# V3_USB.net
KiCad netlist of a schematic drawn in Altium Designer
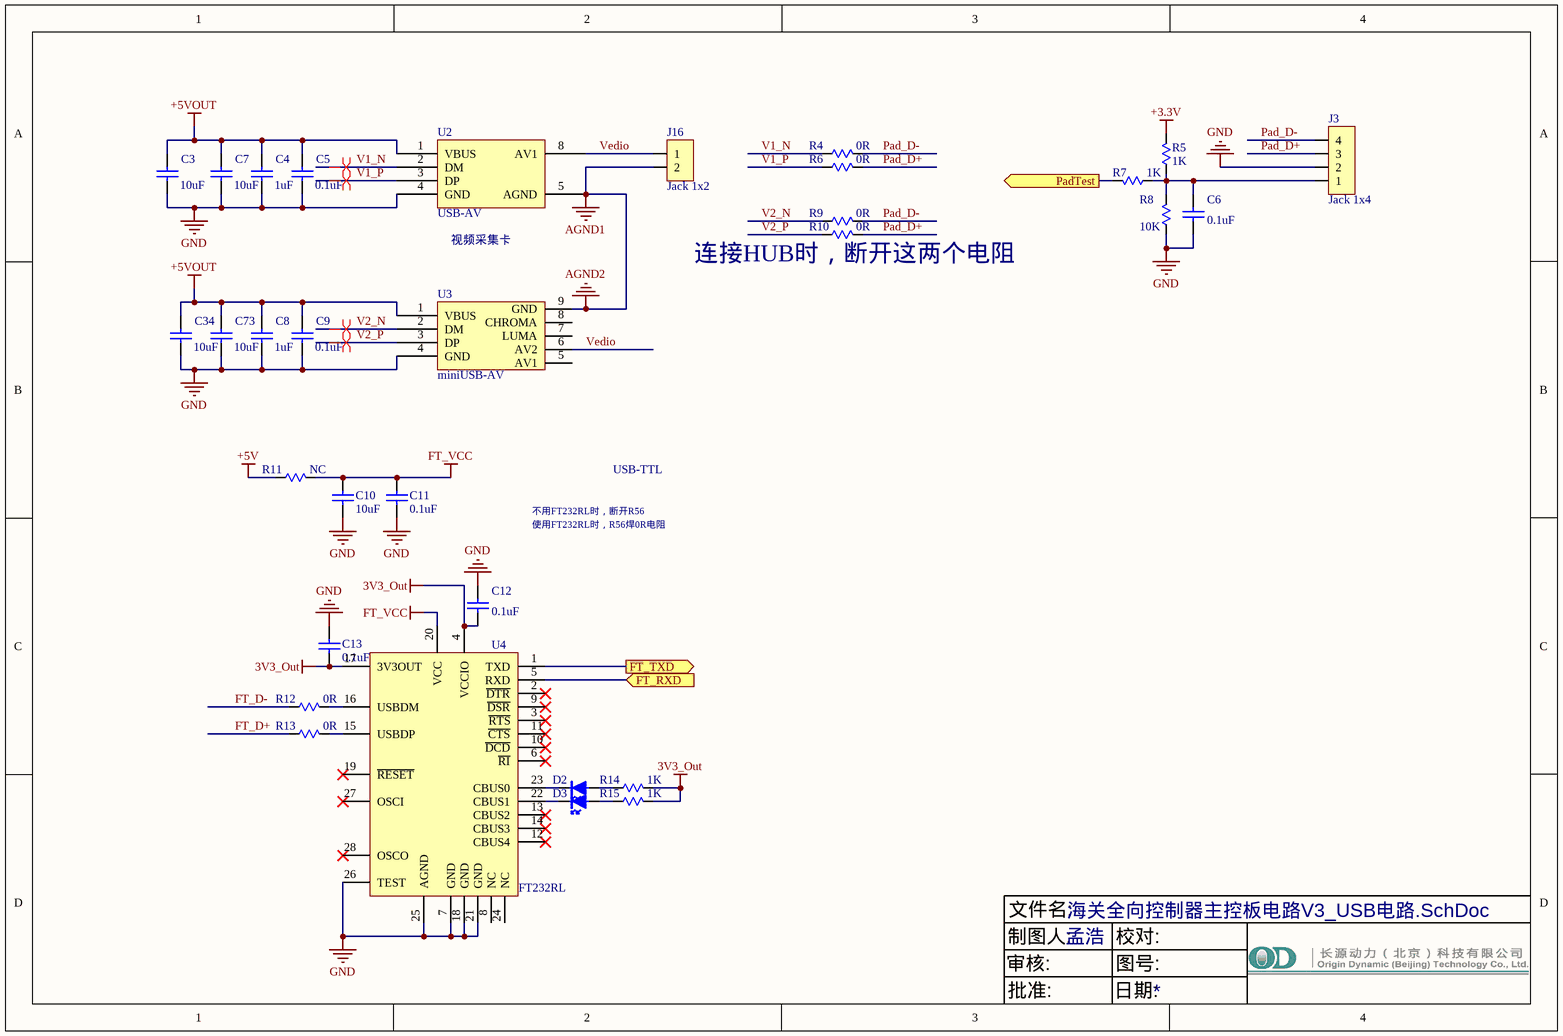
[diagram p0: 海关全向控制器主控板电路V3_USB电路.SchDoc]

(export (version "E")
  (design (tool "Eeschema 10.0.6"))
  (components
    (comp (ref "C3")
      (value "10uF")
      (footprint "C0805")
      (description "CAP")
      (fields (field (name "PUBLISHER") "Altium Limited"))
      (libsource (lib "Passive Components Class") (part "CAP"))
    )
    (comp (ref "C4")
      (value "1uF")
      (footprint "C0805")
      (description "CAP")
      (fields (field (name "PUBLISHER") "Altium Limited"))
      (libsource (lib "Passive Components Class") (part "CAP"))
    )
    (comp (ref "C5") (value "0.1uF") (footprint "C0805") (libsource (lib "SMD") (part "Cap Semi")))
    (comp (ref "C6")
      (value "0.1uF")
      (footprint "C0805")
      (description "Capacitor")
      (fields (field (name "PUBLISHER") "Altium Limited"))
      (libsource (lib "Miscellaneous Devices") (part "Cap"))
    )
    (comp (ref "C7")
      (value "10uF")
      (footprint "C0805")
      (description "CAP")
      (fields (field (name "PUBLISHER") "Altium Limited"))
      (libsource (lib "Passive Components Class") (part "CAP"))
    )
    (comp (ref "C8")
      (value "1uF")
      (footprint "C0805")
      (description "CAP")
      (fields (field (name "PUBLISHER") "Altium Limited"))
      (libsource (lib "Passive Components Class") (part "CAP"))
    )
    (comp (ref "C9") (value "0.1uF") (footprint "C0805") (libsource (lib "SMD") (part "Cap Semi")))
    (comp (ref "C10")
      (value "10uF")
      (footprint "C0805")
      (description "CAP")
      (fields (field (name "PUBLISHER") "Altium Limited"))
      (libsource (lib "Passive Components Class") (part "CAP"))
    )
    (comp (ref "C11") (value "0.1uF") (footprint "C0805") (libsource (lib "SMD") (part "Cap Semi")))
    (comp (ref "C12")
      (value "0.1uF")
      (footprint "C0805")
      (description "Capacitor")
      (fields (field (name "PUBLISHER") "Altium Limited"))
      (libsource (lib "Miscellaneous Devices") (part "Cap"))
    )
    (comp (ref "C13") (value "0.1uF") (footprint "C0805") (libsource (lib "SMD") (part "Cap Semi")))
    (comp (ref "C34")
      (value "10uF")
      (footprint "C0805")
      (description "CAP")
      (fields (field (name "PUBLISHER") "Altium Limited"))
      (libsource (lib "Passive Components Class") (part "CAP"))
    )
    (comp (ref "C73")
      (value "10uF")
      (footprint "C0805")
      (description "CAP")
      (fields (field (name "PUBLISHER") "Altium Limited"))
      (libsource (lib "Passive Components Class") (part "CAP"))
    )
    (comp (ref "D2")
      (value "LED")
      (footprint "LED0603")
      (libsource (lib "Passive Components Class") (part "LED"))
    )
    (comp (ref "D3")
      (value "LED")
      (footprint "LED0603")
      (libsource (lib "Passive Components Class") (part "LED"))
    )
    (comp (ref "J3")
      (value "Jack 1x4")
      (footprint "35363-0460")
      (description "插座")
      (libsource (lib "Connector") (part "Jack 1x4"))
    )
    (comp (ref "J16")
      (value "Jack 1x2")
      (footprint "35363-0260")
      (description "插座")
      (libsource (lib "Connector") (part "Jack 1x2"))
    )
    (comp (ref "R4")
      (value "0R")
      (footprint "R0805")
      (description "Resistor")
      (fields (field (name "PUBLISHER") "Altium Limited"))
      (libsource (lib "Temp") (part "Res"))
    )
    (comp (ref "R5")
      (value "1K")
      (footprint "R0805")
      (description "Resistor")
      (fields (field (name "PUBLISHER") "Altium Limited"))
      (libsource (lib "Temp") (part "Res"))
    )
    (comp (ref "R6")
      (value "0R")
      (footprint "R0805")
      (description "Resistor")
      (fields (field (name "PUBLISHER") "Altium Limited"))
      (libsource (lib "Temp") (part "Res"))
    )
    (comp (ref "R7")
      (value "1K")
      (footprint "R0805")
      (description "Resistor")
      (fields (field (name "PUBLISHER") "Altium Limited"))
      (libsource (lib "Temp") (part "Res"))
    )
    (comp (ref "R8")
      (value "10K")
      (footprint "R0805")
      (description "Resistor")
      (fields (field (name "PUBLISHER") "Altium Limited"))
      (libsource (lib "Temp") (part "Res"))
    )
    (comp (ref "R9")
      (value "0R")
      (footprint "R0805")
      (description "Resistor")
      (fields (field (name "PUBLISHER") "Altium Limited"))
      (libsource (lib "Temp") (part "Res"))
    )
    (comp (ref "R10")
      (value "0R")
      (footprint "R0805")
      (description "Resistor")
      (fields (field (name "PUBLISHER") "Altium Limited"))
      (libsource (lib "Temp") (part "Res"))
    )
    (comp (ref "R11")
      (value "NC")
      (footprint "R0805")
      (description "Resistor")
      (fields (field (name "PUBLISHER") "Altium Limited"))
      (libsource (lib "Temp") (part "Res"))
    )
    (comp (ref "R12")
      (value "0R")
      (footprint "R0805")
      (description "Resistor")
      (fields (field (name "PUBLISHER") "Altium Limited"))
      (libsource (lib "Temp") (part "Res"))
    )
    (comp (ref "R13")
      (value "0R")
      (footprint "R0805")
      (description "Resistor")
      (fields (field (name "PUBLISHER") "Altium Limited"))
      (libsource (lib "Temp") (part "Res"))
    )
    (comp (ref "R14")
      (value "1K")
      (footprint "R0805")
      (description "Resistor")
      (fields (field (name "PUBLISHER") "Altium Limited"))
      (libsource (lib "Temp") (part "Res"))
    )
    (comp (ref "R15")
      (value "1K")
      (footprint "R0805")
      (description "Resistor")
      (fields (field (name "PUBLISHER") "Altium Limited"))
      (libsource (lib "Temp") (part "Res"))
    )
    (comp (ref "U2") (value "USB-AV") (footprint "USB-AV") (libsource (lib "Module") (part "USB-AV")))
    (comp (ref "U3")
      (value "miniUSB-AV")
      (footprint "miniUSB-AV")
      (libsource (lib "Module") (part "miniUSB-AV"))
    )
    (comp (ref "U4")
      (value "FT232RL")
      (footprint "SSOP-28")
      (libsource (lib "海关全向控制器主控板V2") (part "FT232RL"))
    )
  )
  (nets
    (net (code "1") (name "+3.3V") (class "Default")
      (node (ref "R5") (pin "1") (pinfunction "1_1") (pintype "passive"))
    )
    (net (code "2") (name "+5V") (class "Default")
      (node (ref "R11") (pin "2") (pinfunction "2_2") (pintype "passive"))
    )
    (net (code "3") (name "+5VOUT") (class "Default")
      (node (ref "C3") (pin "1") (pinfunction "1_1") (pintype "passive"))
      (node (ref "C34") (pin "1") (pinfunction "1_1") (pintype "passive"))
      (node (ref "C4") (pin "1") (pinfunction "1_1") (pintype "passive"))
      (node (ref "C5") (pin "2") (pinfunction "2_2") (pintype "passive"))
      (node (ref "C7") (pin "1") (pinfunction "1_1") (pintype "passive"))
      (node (ref "C73") (pin "1") (pinfunction "1_1") (pintype "passive"))
      (node (ref "C8") (pin "1") (pinfunction "1_1") (pintype "passive"))
      (node (ref "C9") (pin "2") (pinfunction "2_2") (pintype "passive"))
      (node (ref "U2") (pin "1") (pinfunction "VBUS_1") (pintype "passive"))
      (node (ref "U3") (pin "1") (pinfunction "VBUS_1") (pintype "passive"))
    )
    (net (code "4") (name "/FT_D+") (class "Default")
      (node (ref "R13") (pin "2") (pinfunction "2_2") (pintype "passive"))
    )
    (net (code "5") (name "/FT_D-") (class "Default")
      (node (ref "R12") (pin "2") (pinfunction "2_2") (pintype "passive"))
    )
    (net (code "6") (name "/FT_RXD") (class "Default")
      (node (ref "U4") (pin "5") (pinfunction "RXD_5") (pintype "passive"))
    )
    (net (code "7") (name "/FT_TXD") (class "Default")
      (node (ref "U4") (pin "1") (pinfunction "TXD_1") (pintype "passive"))
    )
    (net (code "8") (name "/PadTest") (class "Default")
      (node (ref "R7") (pin "1") (pinfunction "1_1") (pintype "passive"))
    )
    (net (code "9") (name "/Pad_D+") (class "Default")
      (node (ref "J3") (pin "3") (pinfunction "3_3") (pintype "passive"))
      (node (ref "R10") (pin "1") (pinfunction "1_1") (pintype "passive"))
      (node (ref "R6") (pin "1") (pinfunction "1_1") (pintype "passive"))
    )
    (net (code "10") (name "/Pad_D-") (class "Default")
      (node (ref "J3") (pin "4") (pinfunction "4_4") (pintype "passive"))
      (node (ref "R4") (pin "1") (pinfunction "1_1") (pintype "passive"))
      (node (ref "R9") (pin "1") (pinfunction "1_1") (pintype "passive"))
    )
    (net (code "11") (name "/V1_N") (class "Default")
      (node (ref "R4") (pin "2") (pinfunction "2_2") (pintype "passive"))
      (node (ref "U2") (pin "2") (pinfunction "DM_2") (pintype "passive"))
    )
    (net (code "12") (name "/V1_P") (class "Default")
      (node (ref "R6") (pin "2") (pinfunction "2_2") (pintype "passive"))
      (node (ref "U2") (pin "3") (pinfunction "DP_3") (pintype "passive"))
    )
    (net (code "13") (name "/V2_N") (class "Default")
      (node (ref "R9") (pin "2") (pinfunction "2_2") (pintype "passive"))
      (node (ref "U3") (pin "2") (pinfunction "DM_2") (pintype "passive"))
    )
    (net (code "14") (name "/V2_P") (class "Default")
      (node (ref "R10") (pin "2") (pinfunction "2_2") (pintype "passive"))
      (node (ref "U3") (pin "3") (pinfunction "DP_3") (pintype "passive"))
    )
    (net (code "15") (name "/Vedio") (class "Default")
      (node (ref "J16") (pin "1") (pinfunction "1_1") (pintype "passive"))
      (node (ref "U2") (pin "8") (pinfunction "AV1_8") (pintype "passive"))
      (node (ref "U3") (pin "6") (pinfunction "AV2_6") (pintype "passive"))
    )
    (net (code "16") (name "3V3_Out") (class "Default")
      (node (ref "C12") (pin "2") (pinfunction "2_2") (pintype "passive"))
      (node (ref "C13") (pin "1") (pinfunction "1_1") (pintype "passive"))
      (node (ref "R14") (pin "1") (pinfunction "1_1") (pintype "passive"))
      (node (ref "R15") (pin "1") (pinfunction "1_1") (pintype "passive"))
      (node (ref "U4") (pin "17") (pinfunction "3V3OUT_17") (pintype "passive"))
      (node (ref "U4") (pin "4") (pinfunction "VCCIO_4") (pintype "passive"))
    )
    (net (code "17") (name "AGND1") (class "Default")
      (node (ref "J16") (pin "2") (pinfunction "2_2") (pintype "passive"))
      (node (ref "U2") (pin "5") (pinfunction "AGND_5") (pintype "passive"))
      (node (ref "U3") (pin "9") (pinfunction "GND_9") (pintype "passive"))
    )
    (net (code "18") (name "FT_VCC") (class "Default")
      (node (ref "C10") (pin "1") (pinfunction "1_1") (pintype "passive"))
      (node (ref "C11") (pin "2") (pinfunction "2_2") (pintype "passive"))
      (node (ref "R11") (pin "1") (pinfunction "1_1") (pintype "passive"))
      (node (ref "U4") (pin "20") (pinfunction "VCC_20") (pintype "passive"))
    )
    (net (code "19") (name "GND") (class "Default")
      (node (ref "C10") (pin "2") (pinfunction "2_2") (pintype "passive"))
      (node (ref "C11") (pin "1") (pinfunction "1_1") (pintype "passive"))
      (node (ref "C12") (pin "1") (pinfunction "1_1") (pintype "passive"))
      (node (ref "C13") (pin "2") (pinfunction "2_2") (pintype "passive"))
      (node (ref "C3") (pin "2") (pinfunction "2_2") (pintype "passive"))
      (node (ref "C34") (pin "2") (pinfunction "2_2") (pintype "passive"))
      (node (ref "C4") (pin "2") (pinfunction "2_2") (pintype "passive"))
      (node (ref "C5") (pin "1") (pinfunction "1_1") (pintype "passive"))
      (node (ref "C6") (pin "2") (pinfunction "2_2") (pintype "passive"))
      (node (ref "C7") (pin "2") (pinfunction "2_2") (pintype "passive"))
      (node (ref "C73") (pin "2") (pinfunction "2_2") (pintype "passive"))
      (node (ref "C8") (pin "2") (pinfunction "2_2") (pintype "passive"))
      (node (ref "C9") (pin "1") (pinfunction "1_1") (pintype "passive"))
      (node (ref "J3") (pin "2") (pinfunction "2_2") (pintype "passive"))
      (node (ref "R8") (pin "2") (pinfunction "2_2") (pintype "passive"))
      (node (ref "U2") (pin "4") (pinfunction "GND_4") (pintype "passive"))
      (node (ref "U3") (pin "4") (pinfunction "GND_4") (pintype "passive"))
      (node (ref "U4") (pin "18") (pinfunction "GND_18") (pintype "passive"))
      (node (ref "U4") (pin "21") (pinfunction "GND_21") (pintype "passive"))
      (node (ref "U4") (pin "25") (pinfunction "AGND_25") (pintype "passive"))
      (node (ref "U4") (pin "26") (pinfunction "TEST_26") (pintype "passive"))
      (node (ref "U4") (pin "7") (pinfunction "GND_7") (pintype "passive"))
    )
    (net (code "20") (name "Net-(C6-Pad1)") (class "Default")
      (node (ref "C6") (pin "1") (pinfunction "1_1") (pintype "passive"))
      (node (ref "J3") (pin "1") (pinfunction "1_1") (pintype "passive"))
      (node (ref "R5") (pin "2") (pinfunction "2_2") (pintype "passive"))
      (node (ref "R7") (pin "2") (pinfunction "2_2") (pintype "passive"))
      (node (ref "R8") (pin "1") (pinfunction "1_1") (pintype "passive"))
    )
    (net (code "21") (name "Net-(D2-A)") (class "Default")
      (node (ref "D2") (pin "1") (pinfunction "A_1") (pintype "passive"))
      (node (ref "R14") (pin "2") (pinfunction "2_2") (pintype "passive"))
    )
    (net (code "22") (name "Net-(D2-K)") (class "Default")
      (node (ref "D2") (pin "2") (pinfunction "K_2") (pintype "passive"))
      (node (ref "U4") (pin "23") (pinfunction "CBUS0_23") (pintype "passive"))
    )
    (net (code "23") (name "Net-(D3-A)") (class "Default")
      (node (ref "D3") (pin "1") (pinfunction "A_1") (pintype "passive"))
      (node (ref "R15") (pin "2") (pinfunction "2_2") (pintype "passive"))
    )
    (net (code "24") (name "Net-(D3-K)") (class "Default")
      (node (ref "D3") (pin "2") (pinfunction "K_2") (pintype "passive"))
      (node (ref "U4") (pin "22") (pinfunction "CBUS1_22") (pintype "passive"))
    )
    (net (code "25") (name "Net-(U4-USBDM)") (class "Default")
      (node (ref "R12") (pin "1") (pinfunction "1_1") (pintype "passive"))
      (node (ref "U4") (pin "16") (pinfunction "USBDM_16") (pintype "passive"))
    )
    (net (code "26") (name "Net-(U4-USBDP)") (class "Default")
      (node (ref "R13") (pin "1") (pinfunction "1_1") (pintype "passive"))
      (node (ref "U4") (pin "15") (pinfunction "USBDP_15") (pintype "passive"))
    )
    (net (code "27") (name "unconnected-(U3-AV1-Pad5)") (class "Default")
      (node (ref "U3") (pin "5") (pinfunction "AV1_5") (pintype "passive"))
    )
    (net (code "28") (name "unconnected-(U3-CHROMA-Pad8)") (class "Default")
      (node (ref "U3") (pin "8") (pinfunction "CHROMA_8") (pintype "passive"))
    )
    (net (code "29") (name "unconnected-(U3-LUMA-Pad7)") (class "Default")
      (node (ref "U3") (pin "7") (pinfunction "LUMA_7") (pintype "passive"))
    )
    (net (code "30") (name "unconnected-(U4-CBUS2-Pad13)") (class "Default")
      (node (ref "U4") (pin "13") (pinfunction "CBUS2_13") (pintype "passive+no_connect"))
    )
    (net (code "31") (name "unconnected-(U4-CBUS3-Pad14)") (class "Default")
      (node (ref "U4") (pin "14") (pinfunction "CBUS3_14") (pintype "passive+no_connect"))
    )
    (net (code "32") (name "unconnected-(U4-CBUS4-Pad12)") (class "Default")
      (node (ref "U4") (pin "12") (pinfunction "CBUS4_12") (pintype "passive+no_connect"))
    )
    (net (code "33") (name "unconnected-(U4-NC-Pad8)") (class "Default")
      (node (ref "U4") (pin "8") (pinfunction "NC_8") (pintype "passive"))
    )
    (net (code "34") (name "unconnected-(U4-NC-Pad24)") (class "Default")
      (node (ref "U4") (pin "24") (pinfunction "NC_24") (pintype "passive"))
    )
    (net (code "35") (name "unconnected-(U4-OSCI-Pad27)") (class "Default")
      (node (ref "U4") (pin "27") (pinfunction "OSCI_27") (pintype "passive+no_connect"))
    )
    (net (code "36") (name "unconnected-(U4-OSCO-Pad28)") (class "Default")
      (node (ref "U4") (pin "28") (pinfunction "OSCO_28") (pintype "passive+no_connect"))
    )
    (net (code "37") (name "unconnected-(U4-~{CTS}-Pad11)") (class "Default")
      (node (ref "U4") (pin "11") (pinfunction "~{CTS}_11") (pintype "passive+no_connect"))
    )
    (net (code "38") (name "unconnected-(U4-~{DCD}-Pad10)") (class "Default")
      (node (ref "U4") (pin "10") (pinfunction "~{DCD}_10") (pintype "passive+no_connect"))
    )
    (net (code "39") (name "unconnected-(U4-~{DSR}-Pad9)") (class "Default")
      (node (ref "U4") (pin "9") (pinfunction "~{DSR}_9") (pintype "passive+no_connect"))
    )
    (net (code "40") (name "unconnected-(U4-~{DTR}-Pad2)") (class "Default")
      (node (ref "U4") (pin "2") (pinfunction "~{DTR}_2") (pintype "passive+no_connect"))
    )
    (net (code "41") (name "unconnected-(U4-~{RESET}-Pad19)") (class "Default")
      (node (ref "U4") (pin "19") (pinfunction "~{RESET}_19") (pintype "passive+no_connect"))
    )
    (net (code "42") (name "unconnected-(U4-~{RI}-Pad6)") (class "Default")
      (node (ref "U4") (pin "6") (pinfunction "~{RI}_6") (pintype "passive+no_connect"))
    )
    (net (code "43") (name "unconnected-(U4-~{RTS}-Pad3)") (class "Default")
      (node (ref "U4") (pin "3") (pinfunction "~{RTS}_3") (pintype "passive+no_connect"))
    )
  )
)
